# Phase.net
KiCad netlist of a schematic drawn in Altium Designer
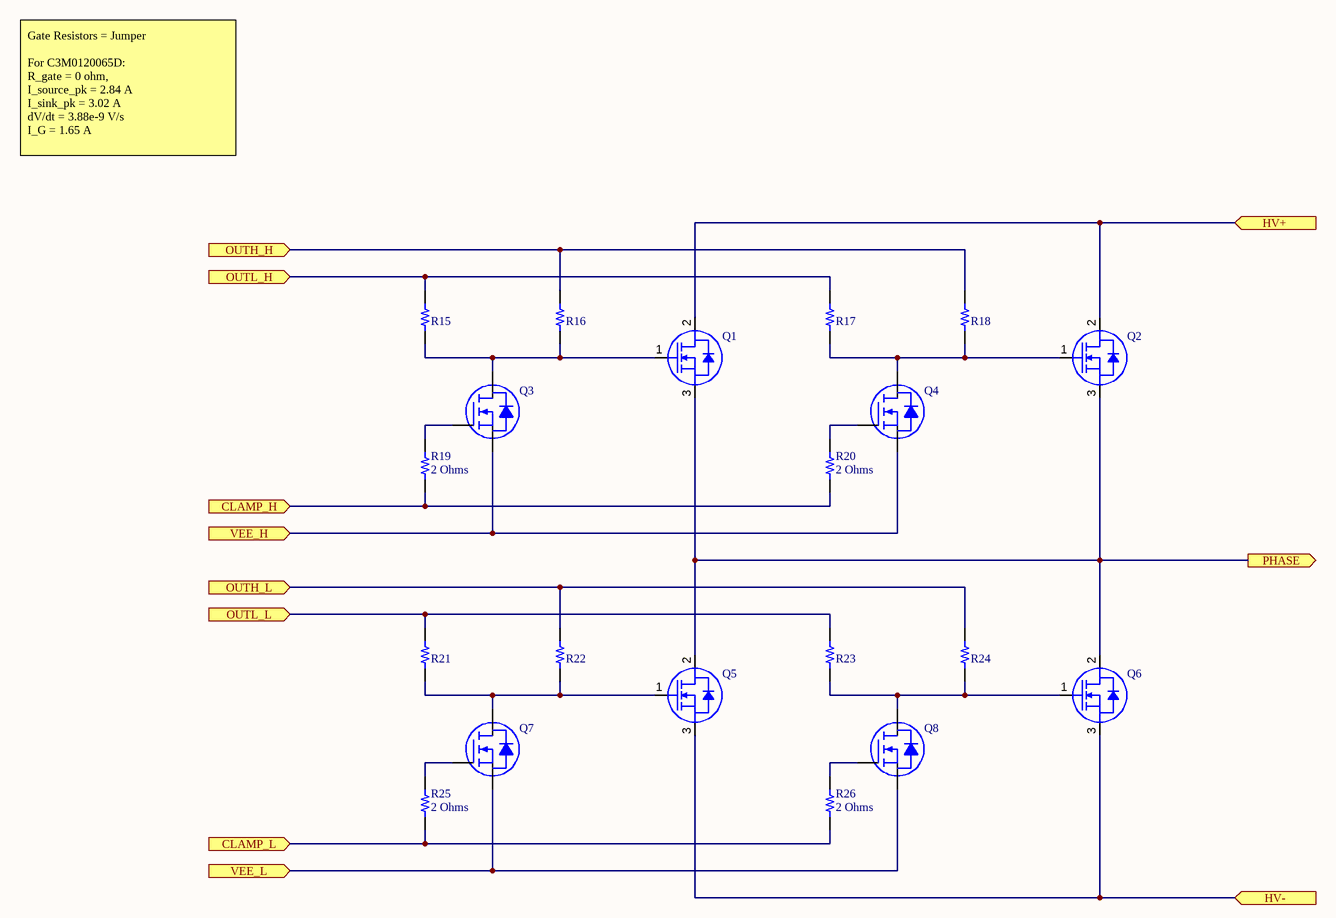
[diagram p0: Phase.SchDoc]

(export (version "E")
  (design (tool "Eeschema 10.0.6"))
  (components
    (comp (ref "Q1")
      (value "C3M0120065D")
      (description "N-Channel 650 V 22A (Tc) 98W (Tc) Through Hole TO-247-3")
      (libsource (lib "3PO") (part "C3M0120065D"))
    )
    (comp (ref "Q2")
      (value "C3M0120065D")
      (description "N-Channel 650 V 22A (Tc) 98W (Tc) Through Hole TO-247-3")
      (libsource (lib "3PO") (part "C3M0120065D"))
    )
    (comp (ref "Q3")
      (value "IRFML8244TRPBF")
      (footprint "INFINEON SOT-23-3")
      (description "MOSFET N-CH 25V 5.8A SOT23")
      (fields (field (name "MANUFACTURER") "Infineon Technologies"))
      (libsource (lib "Celestial Altium Library - altium_library") (part "INFINEON MOSFET N-CH SOT-23-3 GSD"))
    )
    (comp (ref "Q4")
      (value "IRFML8244TRPBF")
      (footprint "INFINEON SOT-23-3")
      (description "MOSFET N-CH 25V 5.8A SOT23")
      (fields (field (name "MANUFACTURER") "Infineon Technologies"))
      (libsource (lib "Celestial Altium Library - altium_library") (part "INFINEON MOSFET N-CH SOT-23-3 GSD"))
    )
    (comp (ref "Q5")
      (value "C3M0120065D")
      (description "N-Channel 650 V 22A (Tc) 98W (Tc) Through Hole TO-247-3")
      (libsource (lib "3PO") (part "C3M0120065D"))
    )
    (comp (ref "Q6")
      (value "C3M0120065D")
      (description "N-Channel 650 V 22A (Tc) 98W (Tc) Through Hole TO-247-3")
      (libsource (lib "3PO") (part "C3M0120065D"))
    )
    (comp (ref "Q7")
      (value "IRFML8244TRPBF")
      (footprint "INFINEON SOT-23-3")
      (description "MOSFET N-CH 25V 5.8A SOT23")
      (fields (field (name "MANUFACTURER") "Infineon Technologies"))
      (libsource (lib "Celestial Altium Library - altium_library") (part "INFINEON MOSFET N-CH SOT-23-3 GSD"))
    )
    (comp (ref "Q8")
      (value "IRFML8244TRPBF")
      (footprint "INFINEON SOT-23-3")
      (description "MOSFET N-CH 25V 5.8A SOT23")
      (fields (field (name "MANUFACTURER") "Infineon Technologies"))
      (libsource (lib "Celestial Altium Library - altium_library") (part "INFINEON MOSFET N-CH SOT-23-3 GSD"))
    )
    (comp (ref "R15")
      (value "~")
      (footprint "RES 0805_2012")
      (description "RES 0 OHM JUMPER 0805")
      (fields (field (name "PART NUMBER") "5107") (field (name "MANUFACTURER") "Keystone Electronics"))
      (libsource (lib "Celestial Altium Library - altium_library") (part "Resistor"))
    )
    (comp (ref "R16")
      (value "~")
      (footprint "RES 0805_2012")
      (description "RES 0 OHM JUMPER 0805")
      (fields (field (name "PART NUMBER") "5107") (field (name "MANUFACTURER") "Keystone Electronics"))
      (libsource (lib "Celestial Altium Library - altium_library") (part "Resistor"))
    )
    (comp (ref "R17")
      (value "~")
      (footprint "RES 0805_2012")
      (description "RES 0 OHM JUMPER 0805")
      (fields (field (name "PART NUMBER") "5107") (field (name "MANUFACTURER") "Keystone Electronics"))
      (libsource (lib "Celestial Altium Library - altium_library") (part "Resistor"))
    )
    (comp (ref "R18")
      (value "~")
      (footprint "RES 0805_2012")
      (description "RES 0 OHM JUMPER 0805")
      (fields (field (name "PART NUMBER") "5107") (field (name "MANUFACTURER") "Keystone Electronics"))
      (libsource (lib "Celestial Altium Library - altium_library") (part "Resistor"))
    )
    (comp (ref "R19")
      (value "2 Ohms")
      (footprint "RES 0805_2012")
      (description "RES SMD 2 OHM 5% 1/8W 0805")
      (fields (field (name "PART NUMBER") "CRCW08052R00JNEA") (field (name "MANUFACTURER") "Vishay Dale"))
      (libsource (lib "Celestial Altium Library - altium_library") (part "Resistor"))
    )
    (comp (ref "R20")
      (value "2 Ohms")
      (footprint "RES 0805_2012")
      (description "RES SMD 2 OHM 5% 1/8W 0805")
      (fields (field (name "PART NUMBER") "CRCW08052R00JNEA") (field (name "MANUFACTURER") "Vishay Dale"))
      (libsource (lib "Celestial Altium Library - altium_library") (part "Resistor"))
    )
    (comp (ref "R21")
      (value "~")
      (footprint "RES 0805_2012")
      (description "RES 0 OHM JUMPER 0805")
      (fields (field (name "PART NUMBER") "5107") (field (name "MANUFACTURER") "Keystone Electronics"))
      (libsource (lib "Celestial Altium Library - altium_library") (part "Resistor"))
    )
    (comp (ref "R22")
      (value "~")
      (footprint "RES 0805_2012")
      (description "RES 0 OHM JUMPER 0805")
      (fields (field (name "PART NUMBER") "5107") (field (name "MANUFACTURER") "Keystone Electronics"))
      (libsource (lib "Celestial Altium Library - altium_library") (part "Resistor"))
    )
    (comp (ref "R23")
      (value "~")
      (footprint "RES 0805_2012")
      (description "RES 0 OHM JUMPER 0805")
      (fields (field (name "PART NUMBER") "5107") (field (name "MANUFACTURER") "Keystone Electronics"))
      (libsource (lib "Celestial Altium Library - altium_library") (part "Resistor"))
    )
    (comp (ref "R24")
      (value "~")
      (footprint "RES 0805_2012")
      (description "RES 0 OHM JUMPER 0805")
      (fields (field (name "PART NUMBER") "5107") (field (name "MANUFACTURER") "Keystone Electronics"))
      (libsource (lib "Celestial Altium Library - altium_library") (part "Resistor"))
    )
    (comp (ref "R25")
      (value "2 Ohms")
      (footprint "RES 0805_2012")
      (description "RES SMD 2 OHM 5% 1/8W 0805")
      (fields (field (name "PART NUMBER") "CRCW08052R00JNEA") (field (name "MANUFACTURER") "Vishay Dale"))
      (libsource (lib "Celestial Altium Library - altium_library") (part "Resistor"))
    )
    (comp (ref "R26")
      (value "2 Ohms")
      (footprint "RES 0805_2012")
      (description "RES SMD 2 OHM 5% 1/8W 0805")
      (fields (field (name "PART NUMBER") "CRCW08052R00JNEA") (field (name "MANUFACTURER") "Vishay Dale"))
      (libsource (lib "Celestial Altium Library - altium_library") (part "Resistor"))
    )
  )
  (nets
    (net (code "1") (name "/CLAMP_H") (class "Default")
      (node (ref "R19") (pin "1") (pinfunction "1_1") (pintype "passive"))
      (node (ref "R20") (pin "1") (pinfunction "1_1") (pintype "passive"))
    )
    (net (code "2") (name "/CLAMP_L") (class "Default")
      (node (ref "R25") (pin "1") (pinfunction "1_1") (pintype "passive"))
      (node (ref "R26") (pin "1") (pinfunction "1_1") (pintype "passive"))
    )
    (net (code "3") (name "/HV+") (class "Default")
      (node (ref "Q1") (pin "2") (pinfunction "DRAIN_2") (pintype "passive"))
      (node (ref "Q2") (pin "2") (pinfunction "DRAIN_2") (pintype "passive"))
    )
    (net (code "4") (name "/HV-") (class "Default")
      (node (ref "Q5") (pin "3") (pinfunction "SOURCE_3") (pintype "passive"))
      (node (ref "Q6") (pin "3") (pinfunction "SOURCE_3") (pintype "passive"))
    )
    (net (code "5") (name "/OUTH_H") (class "Default")
      (node (ref "R16") (pin "1") (pinfunction "1_1") (pintype "passive"))
      (node (ref "R18") (pin "1") (pinfunction "1_1") (pintype "passive"))
    )
    (net (code "6") (name "/OUTH_L") (class "Default")
      (node (ref "R22") (pin "1") (pinfunction "1_1") (pintype "passive"))
      (node (ref "R24") (pin "1") (pinfunction "1_1") (pintype "passive"))
    )
    (net (code "7") (name "/OUTL_H") (class "Default")
      (node (ref "R15") (pin "1") (pinfunction "1_1") (pintype "passive"))
      (node (ref "R17") (pin "1") (pinfunction "1_1") (pintype "passive"))
    )
    (net (code "8") (name "/OUTL_L") (class "Default")
      (node (ref "R21") (pin "1") (pinfunction "1_1") (pintype "passive"))
      (node (ref "R23") (pin "1") (pinfunction "1_1") (pintype "passive"))
    )
    (net (code "9") (name "/PHASE") (class "Default")
      (node (ref "Q1") (pin "3") (pinfunction "SOURCE_3") (pintype "passive"))
      (node (ref "Q2") (pin "3") (pinfunction "SOURCE_3") (pintype "passive"))
      (node (ref "Q5") (pin "2") (pinfunction "DRAIN_2") (pintype "passive"))
      (node (ref "Q6") (pin "2") (pinfunction "DRAIN_2") (pintype "passive"))
    )
    (net (code "10") (name "/VEE_H") (class "Default")
      (node (ref "Q3") (pin "2") (pinfunction "S_2") (pintype "passive"))
      (node (ref "Q4") (pin "2") (pinfunction "S_2") (pintype "passive"))
    )
    (net (code "11") (name "/VEE_L") (class "Default")
      (node (ref "Q7") (pin "2") (pinfunction "S_2") (pintype "passive"))
      (node (ref "Q8") (pin "2") (pinfunction "S_2") (pintype "passive"))
    )
    (net (code "12") (name "Net-(Q1-GATE)") (class "Default")
      (node (ref "Q1") (pin "1") (pinfunction "GATE_1") (pintype "passive"))
      (node (ref "Q3") (pin "3") (pinfunction "D_3") (pintype "passive"))
      (node (ref "R15") (pin "2") (pinfunction "2_2") (pintype "passive"))
      (node (ref "R16") (pin "2") (pinfunction "2_2") (pintype "passive"))
    )
    (net (code "13") (name "Net-(Q2-GATE)") (class "Default")
      (node (ref "Q2") (pin "1") (pinfunction "GATE_1") (pintype "passive"))
      (node (ref "Q4") (pin "3") (pinfunction "D_3") (pintype "passive"))
      (node (ref "R17") (pin "2") (pinfunction "2_2") (pintype "passive"))
      (node (ref "R18") (pin "2") (pinfunction "2_2") (pintype "passive"))
    )
    (net (code "14") (name "Net-(Q3-G)") (class "Default")
      (node (ref "Q3") (pin "1") (pinfunction "G_1") (pintype "passive"))
      (node (ref "R19") (pin "2") (pinfunction "2_2") (pintype "passive"))
    )
    (net (code "15") (name "Net-(Q4-G)") (class "Default")
      (node (ref "Q4") (pin "1") (pinfunction "G_1") (pintype "passive"))
      (node (ref "R20") (pin "2") (pinfunction "2_2") (pintype "passive"))
    )
    (net (code "16") (name "Net-(Q5-GATE)") (class "Default")
      (node (ref "Q5") (pin "1") (pinfunction "GATE_1") (pintype "passive"))
      (node (ref "Q7") (pin "3") (pinfunction "D_3") (pintype "passive"))
      (node (ref "R21") (pin "2") (pinfunction "2_2") (pintype "passive"))
      (node (ref "R22") (pin "2") (pinfunction "2_2") (pintype "passive"))
    )
    (net (code "17") (name "Net-(Q6-GATE)") (class "Default")
      (node (ref "Q6") (pin "1") (pinfunction "GATE_1") (pintype "passive"))
      (node (ref "Q8") (pin "3") (pinfunction "D_3") (pintype "passive"))
      (node (ref "R23") (pin "2") (pinfunction "2_2") (pintype "passive"))
      (node (ref "R24") (pin "2") (pinfunction "2_2") (pintype "passive"))
    )
    (net (code "18") (name "Net-(Q7-G)") (class "Default")
      (node (ref "Q7") (pin "1") (pinfunction "G_1") (pintype "passive"))
      (node (ref "R25") (pin "2") (pinfunction "2_2") (pintype "passive"))
    )
    (net (code "19") (name "Net-(Q8-G)") (class "Default")
      (node (ref "Q8") (pin "1") (pinfunction "G_1") (pintype "passive"))
      (node (ref "R26") (pin "2") (pinfunction "2_2") (pintype "passive"))
    )
  )
)
